# spartan6-0.net
KiCad netlist of a schematic drawn in Altium Designer
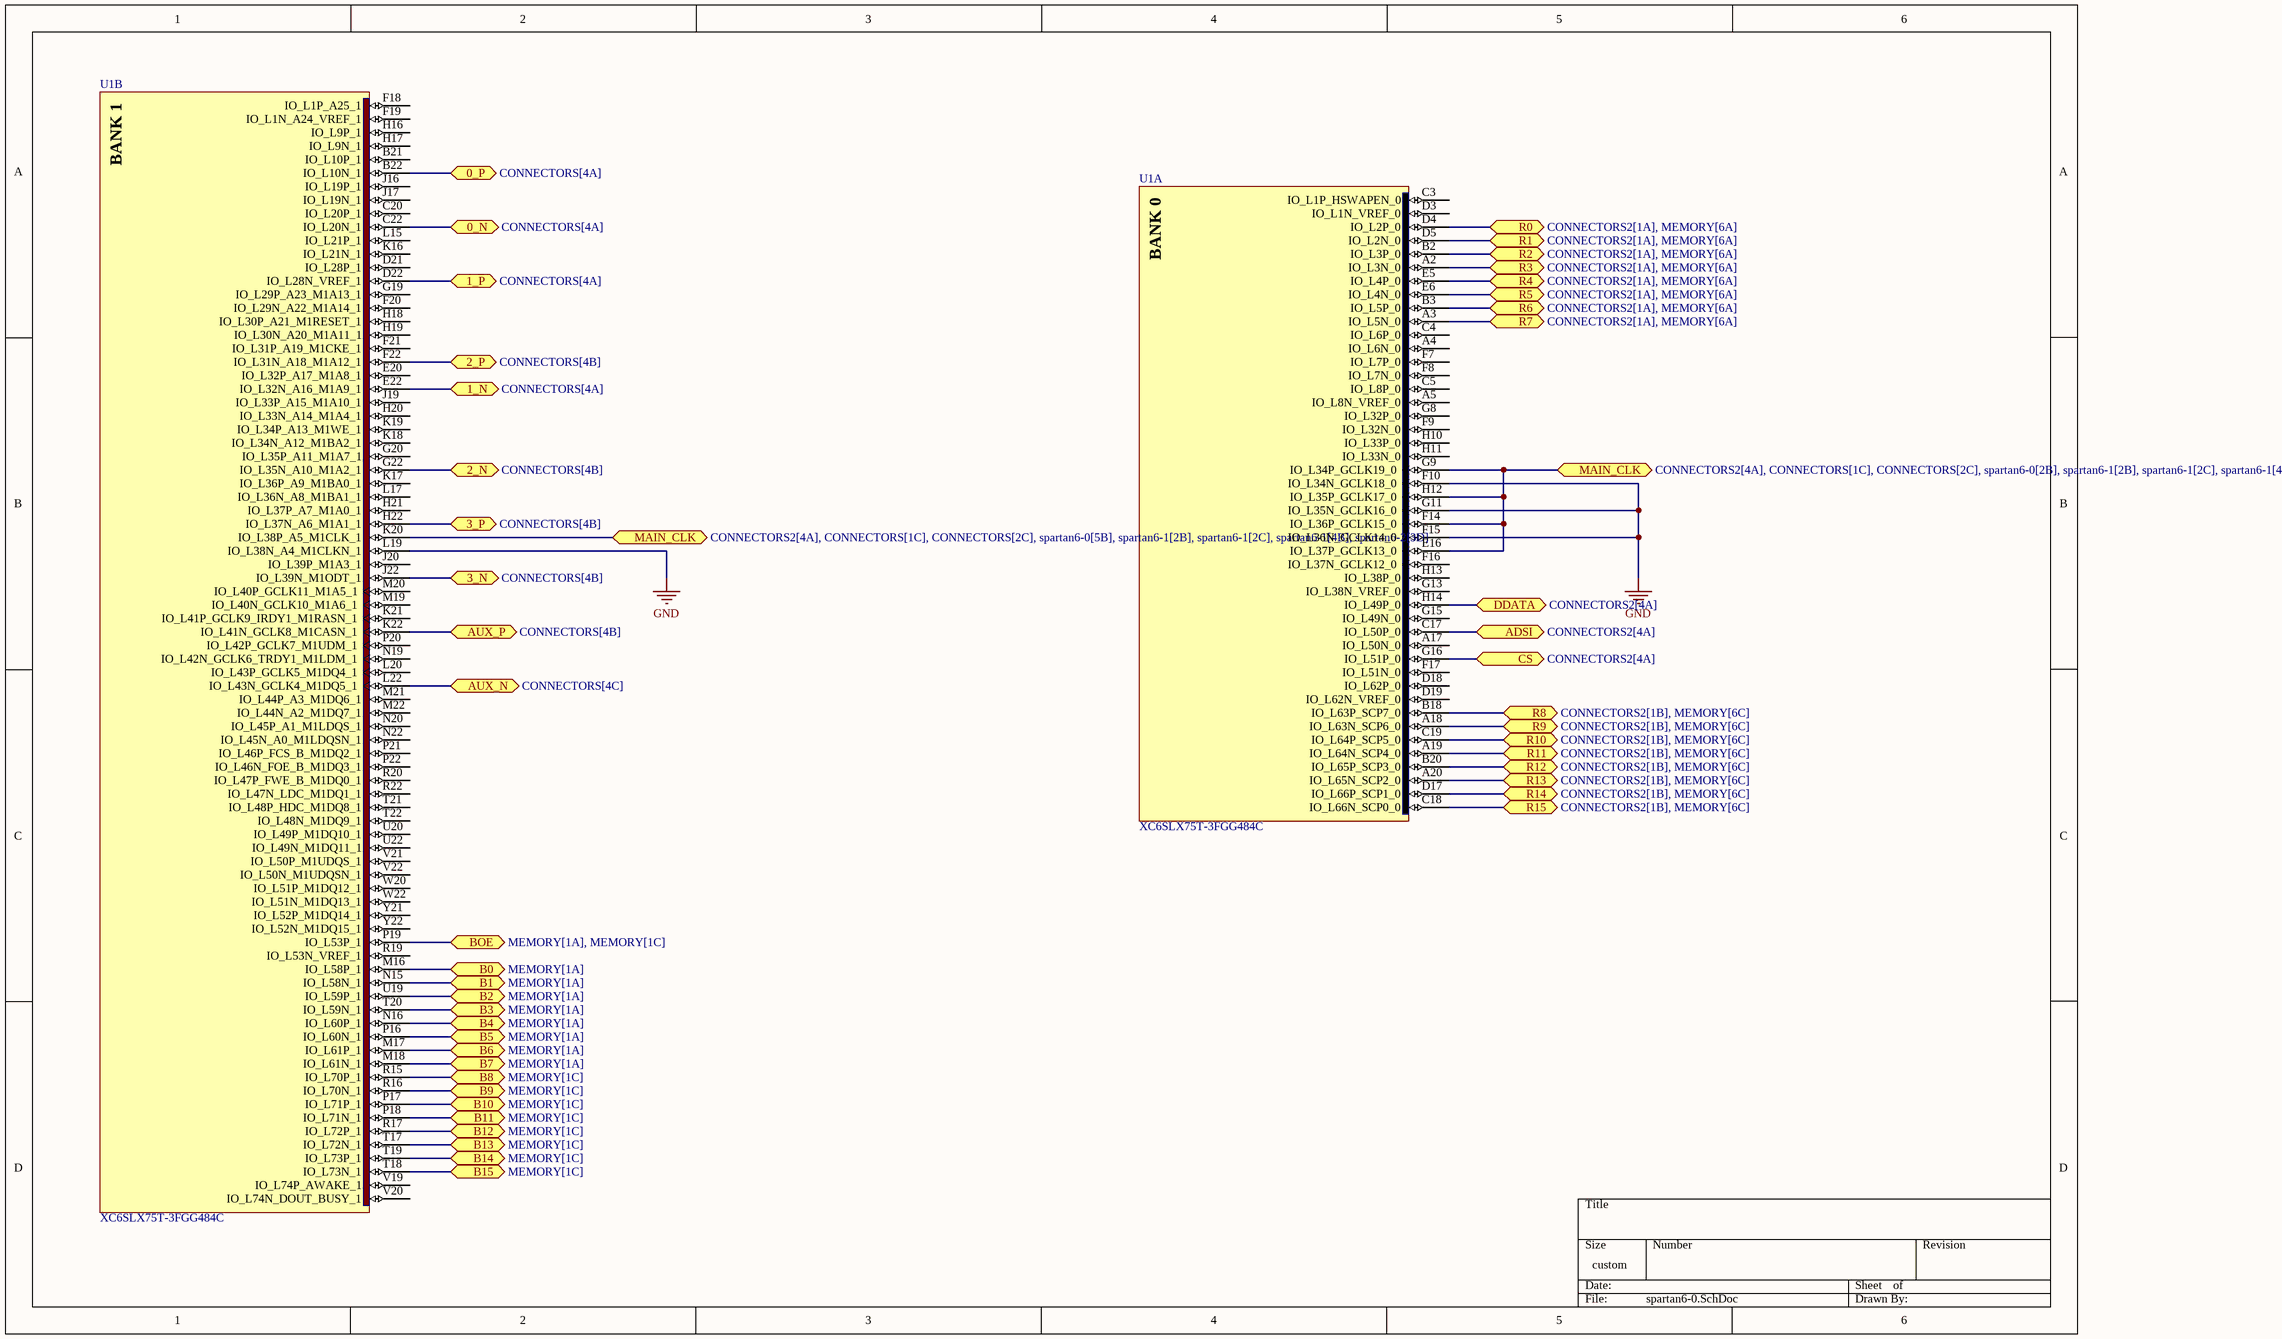
[diagram p0: spartan6-0.SchDoc]

(export (version "E")
  (design (tool "Eeschema 10.0.6"))
  (components
    (comp (ref "U1")
      (value "XC6SLX75T-3FGG484C")
      (footprint "FGG484")
      (libsource (lib "Altium Content Vault") (part "FPGA-XSP6-XC6SLX75T-GA484"))
    )
  )
  (nets
    (net (code "1") (name "/0_N") (class "Default")
      (node (ref "U1") (pin "C22") (pinfunction "IO_L20N_1_C22") (pintype "bidirectional"))
    )
    (net (code "2") (name "/0_P") (class "Default")
      (node (ref "U1") (pin "B22") (pinfunction "IO_L10N_1_B22") (pintype "bidirectional"))
    )
    (net (code "3") (name "/1_N") (class "Default")
      (node (ref "U1") (pin "E22") (pinfunction "IO_L32N_A16_M1A9_1_E22") (pintype "bidirectional"))
    )
    (net (code "4") (name "/1_P") (class "Default")
      (node (ref "U1") (pin "D22") (pinfunction "IO_L28N_VREF_1_D22") (pintype "bidirectional"))
    )
    (net (code "5") (name "/2_N") (class "Default")
      (node (ref "U1") (pin "G22") (pinfunction "IO_L35N_A10_M1A2_1_G22") (pintype "bidirectional"))
    )
    (net (code "6") (name "/2_P") (class "Default")
      (node (ref "U1") (pin "F22") (pinfunction "IO_L31N_A18_M1A12_1_F22") (pintype "bidirectional"))
    )
    (net (code "7") (name "/3_N") (class "Default")
      (node (ref "U1") (pin "J22") (pinfunction "IO_L39N_M1ODT_1_J22") (pintype "bidirectional"))
    )
    (net (code "8") (name "/3_P") (class "Default")
      (node (ref "U1") (pin "H22") (pinfunction "IO_L37N_A6_M1A1_1_H22") (pintype "bidirectional"))
    )
    (net (code "9") (name "/ADSI") (class "Default")
      (node (ref "U1") (pin "C17") (pinfunction "IO_L50P_0_C17") (pintype "bidirectional"))
    )
    (net (code "10") (name "/AUX_N") (class "Default")
      (node (ref "U1") (pin "L22") (pinfunction "IO_L43N_GCLK4_M1DQ5_1_L22") (pintype "bidirectional"))
    )
    (net (code "11") (name "/AUX_P") (class "Default")
      (node (ref "U1") (pin "K22") (pinfunction "IO_L41N_GCLK8_M1CASN_1_K22") (pintype "bidirectional"))
    )
    (net (code "12") (name "/B0") (class "Default")
      (node (ref "U1") (pin "M16") (pinfunction "IO_L58P_1_M16") (pintype "bidirectional"))
    )
    (net (code "13") (name "/B1") (class "Default")
      (node (ref "U1") (pin "N15") (pinfunction "IO_L58N_1_N15") (pintype "bidirectional"))
    )
    (net (code "14") (name "/B2") (class "Default")
      (node (ref "U1") (pin "U19") (pinfunction "IO_L59P_1_U19") (pintype "bidirectional"))
    )
    (net (code "15") (name "/B3") (class "Default")
      (node (ref "U1") (pin "T20") (pinfunction "IO_L59N_1_T20") (pintype "bidirectional"))
    )
    (net (code "16") (name "/B4") (class "Default")
      (node (ref "U1") (pin "N16") (pinfunction "IO_L60P_1_N16") (pintype "bidirectional"))
    )
    (net (code "17") (name "/B5") (class "Default")
      (node (ref "U1") (pin "P16") (pinfunction "IO_L60N_1_P16") (pintype "bidirectional"))
    )
    (net (code "18") (name "/B6") (class "Default")
      (node (ref "U1") (pin "M17") (pinfunction "IO_L61P_1_M17") (pintype "bidirectional"))
    )
    (net (code "19") (name "/B7") (class "Default")
      (node (ref "U1") (pin "M18") (pinfunction "IO_L61N_1_M18") (pintype "bidirectional"))
    )
    (net (code "20") (name "/B8") (class "Default")
      (node (ref "U1") (pin "R15") (pinfunction "IO_L70P_1_R15") (pintype "bidirectional"))
    )
    (net (code "21") (name "/B9") (class "Default")
      (node (ref "U1") (pin "R16") (pinfunction "IO_L70N_1_R16") (pintype "bidirectional"))
    )
    (net (code "22") (name "/B10") (class "Default")
      (node (ref "U1") (pin "P17") (pinfunction "IO_L71P_1_P17") (pintype "bidirectional"))
    )
    (net (code "23") (name "/B11") (class "Default")
      (node (ref "U1") (pin "P18") (pinfunction "IO_L71N_1_P18") (pintype "bidirectional"))
    )
    (net (code "24") (name "/B12") (class "Default")
      (node (ref "U1") (pin "R17") (pinfunction "IO_L72P_1_R17") (pintype "bidirectional"))
    )
    (net (code "25") (name "/B13") (class "Default")
      (node (ref "U1") (pin "T17") (pinfunction "IO_L72N_1_T17") (pintype "bidirectional"))
    )
    (net (code "26") (name "/B14") (class "Default")
      (node (ref "U1") (pin "T19") (pinfunction "IO_L73P_1_T19") (pintype "bidirectional"))
    )
    (net (code "27") (name "/B15") (class "Default")
      (node (ref "U1") (pin "T18") (pinfunction "IO_L73N_1_T18") (pintype "bidirectional"))
    )
    (net (code "28") (name "/BOE") (class "Default")
      (node (ref "U1") (pin "P19") (pinfunction "IO_L53P_1_P19") (pintype "bidirectional"))
    )
    (net (code "29") (name "/CS") (class "Default")
      (node (ref "U1") (pin "G16") (pinfunction "IO_L51P_0_G16") (pintype "bidirectional"))
    )
    (net (code "30") (name "/DDATA") (class "Default")
      (node (ref "U1") (pin "H14") (pinfunction "IO_L49P_0_H14") (pintype "bidirectional"))
    )
    (net (code "31") (name "/MAIN_CLK") (class "Default")
      (node (ref "U1") (pin "E16") (pinfunction "IO_L37P_GCLK13_0_E16") (pintype "bidirectional"))
      (node (ref "U1") (pin "F14") (pinfunction "IO_L36P_GCLK15_0_F14") (pintype "bidirectional"))
      (node (ref "U1") (pin "G9") (pinfunction "IO_L34P_GCLK19_0_G9") (pintype "bidirectional"))
      (node (ref "U1") (pin "H12") (pinfunction "IO_L35P_GCLK17_0_H12") (pintype "bidirectional"))
      (node (ref "U1") (pin "K20") (pinfunction "IO_L38P_A5_M1CLK_1_K20") (pintype "bidirectional"))
    )
    (net (code "32") (name "/R0") (class "Default")
      (node (ref "U1") (pin "D4") (pinfunction "IO_L2P_0_D4") (pintype "bidirectional"))
    )
    (net (code "33") (name "/R1") (class "Default")
      (node (ref "U1") (pin "D5") (pinfunction "IO_L2N_0_D5") (pintype "bidirectional"))
    )
    (net (code "34") (name "/R2") (class "Default")
      (node (ref "U1") (pin "B2") (pinfunction "IO_L3P_0_B2") (pintype "bidirectional"))
    )
    (net (code "35") (name "/R3") (class "Default")
      (node (ref "U1") (pin "A2") (pinfunction "IO_L3N_0_A2") (pintype "bidirectional"))
    )
    (net (code "36") (name "/R4") (class "Default")
      (node (ref "U1") (pin "E5") (pinfunction "IO_L4P_0_E5") (pintype "bidirectional"))
    )
    (net (code "37") (name "/R5") (class "Default")
      (node (ref "U1") (pin "E6") (pinfunction "IO_L4N_0_E6") (pintype "bidirectional"))
    )
    (net (code "38") (name "/R6") (class "Default")
      (node (ref "U1") (pin "B3") (pinfunction "IO_L5P_0_B3") (pintype "bidirectional"))
    )
    (net (code "39") (name "/R7") (class "Default")
      (node (ref "U1") (pin "A3") (pinfunction "IO_L5N_0_A3") (pintype "bidirectional"))
    )
    (net (code "40") (name "/R8") (class "Default")
      (node (ref "U1") (pin "B18") (pinfunction "IO_L63P_SCP7_0_B18") (pintype "bidirectional"))
    )
    (net (code "41") (name "/R9") (class "Default")
      (node (ref "U1") (pin "A18") (pinfunction "IO_L63N_SCP6_0_A18") (pintype "bidirectional"))
    )
    (net (code "42") (name "/R10") (class "Default")
      (node (ref "U1") (pin "C19") (pinfunction "IO_L64P_SCP5_0_C19") (pintype "bidirectional"))
    )
    (net (code "43") (name "/R11") (class "Default")
      (node (ref "U1") (pin "A19") (pinfunction "IO_L64N_SCP4_0_A19") (pintype "bidirectional"))
    )
    (net (code "44") (name "/R12") (class "Default")
      (node (ref "U1") (pin "B20") (pinfunction "IO_L65P_SCP3_0_B20") (pintype "bidirectional"))
    )
    (net (code "45") (name "/R13") (class "Default")
      (node (ref "U1") (pin "A20") (pinfunction "IO_L65N_SCP2_0_A20") (pintype "bidirectional"))
    )
    (net (code "46") (name "/R14") (class "Default")
      (node (ref "U1") (pin "D17") (pinfunction "IO_L66P_SCP1_0_D17") (pintype "bidirectional"))
    )
    (net (code "47") (name "/R15") (class "Default")
      (node (ref "U1") (pin "C18") (pinfunction "IO_L66N_SCP0_0_C18") (pintype "bidirectional"))
    )
    (net (code "48") (name "GND") (class "Default")
      (node (ref "U1") (pin "F10") (pinfunction "IO_L34N_GCLK18_0_F10") (pintype "bidirectional"))
      (node (ref "U1") (pin "F15") (pinfunction "IO_L36N_GCLK14_0_F15") (pintype "bidirectional"))
      (node (ref "U1") (pin "G11") (pinfunction "IO_L35N_GCLK16_0_G11") (pintype "bidirectional"))
      (node (ref "U1") (pin "L19") (pinfunction "IO_L38N_A4_M1CLKN_1_L19") (pintype "bidirectional"))
    )
    (net (code "49") (name "unconnected-(U1A-IO_L1N_VREF_0-PadD3)") (class "Default")
      (node (ref "U1") (pin "D3") (pinfunction "IO_L1N_VREF_0_D3") (pintype "bidirectional"))
    )
    (net (code "50") (name "unconnected-(U1A-IO_L1P_HSWAPEN_0-PadC3)") (class "Default")
      (node (ref "U1") (pin "C3") (pinfunction "IO_L1P_HSWAPEN_0_C3") (pintype "bidirectional"))
    )
    (net (code "51") (name "unconnected-(U1A-IO_L6N_0-PadA4)") (class "Default")
      (node (ref "U1") (pin "A4") (pinfunction "IO_L6N_0_A4") (pintype "bidirectional"))
    )
    (net (code "52") (name "unconnected-(U1A-IO_L6P_0-PadC4)") (class "Default")
      (node (ref "U1") (pin "C4") (pinfunction "IO_L6P_0_C4") (pintype "bidirectional"))
    )
    (net (code "53") (name "unconnected-(U1A-IO_L7N_0-PadF8)") (class "Default")
      (node (ref "U1") (pin "F8") (pinfunction "IO_L7N_0_F8") (pintype "bidirectional"))
    )
    (net (code "54") (name "unconnected-(U1A-IO_L7P_0-PadF7)") (class "Default")
      (node (ref "U1") (pin "F7") (pinfunction "IO_L7P_0_F7") (pintype "bidirectional"))
    )
    (net (code "55") (name "unconnected-(U1A-IO_L8N_VREF_0-PadA5)") (class "Default")
      (node (ref "U1") (pin "A5") (pinfunction "IO_L8N_VREF_0_A5") (pintype "bidirectional"))
    )
    (net (code "56") (name "unconnected-(U1A-IO_L8P_0-PadC5)") (class "Default")
      (node (ref "U1") (pin "C5") (pinfunction "IO_L8P_0_C5") (pintype "bidirectional"))
    )
    (net (code "57") (name "unconnected-(U1A-IO_L32N_0-PadF9)") (class "Default")
      (node (ref "U1") (pin "F9") (pinfunction "IO_L32N_0_F9") (pintype "bidirectional"))
    )
    (net (code "58") (name "unconnected-(U1A-IO_L32P_0-PadG8)") (class "Default")
      (node (ref "U1") (pin "G8") (pinfunction "IO_L32P_0_G8") (pintype "bidirectional"))
    )
    (net (code "59") (name "unconnected-(U1A-IO_L33N_0-PadH11)") (class "Default")
      (node (ref "U1") (pin "H11") (pinfunction "IO_L33N_0_H11") (pintype "bidirectional"))
    )
    (net (code "60") (name "unconnected-(U1A-IO_L33P_0-PadH10)") (class "Default")
      (node (ref "U1") (pin "H10") (pinfunction "IO_L33P_0_H10") (pintype "bidirectional"))
    )
    (net (code "61") (name "unconnected-(U1A-IO_L37N_GCLK12_0-PadF16)") (class "Default")
      (node (ref "U1") (pin "F16") (pinfunction "IO_L37N_GCLK12_0_F16") (pintype "bidirectional"))
    )
    (net (code "62") (name "unconnected-(U1A-IO_L38N_VREF_0-PadG13)") (class "Default")
      (node (ref "U1") (pin "G13") (pinfunction "IO_L38N_VREF_0_G13") (pintype "bidirectional"))
    )
    (net (code "63") (name "unconnected-(U1A-IO_L38P_0-PadH13)") (class "Default")
      (node (ref "U1") (pin "H13") (pinfunction "IO_L38P_0_H13") (pintype "bidirectional"))
    )
    (net (code "64") (name "unconnected-(U1A-IO_L49N_0-PadG15)") (class "Default")
      (node (ref "U1") (pin "G15") (pinfunction "IO_L49N_0_G15") (pintype "bidirectional"))
    )
    (net (code "65") (name "unconnected-(U1A-IO_L50N_0-PadA17)") (class "Default")
      (node (ref "U1") (pin "A17") (pinfunction "IO_L50N_0_A17") (pintype "bidirectional"))
    )
    (net (code "66") (name "unconnected-(U1A-IO_L51N_0-PadF17)") (class "Default")
      (node (ref "U1") (pin "F17") (pinfunction "IO_L51N_0_F17") (pintype "bidirectional"))
    )
    (net (code "67") (name "unconnected-(U1A-IO_L62N_VREF_0-PadD19)") (class "Default")
      (node (ref "U1") (pin "D19") (pinfunction "IO_L62N_VREF_0_D19") (pintype "bidirectional"))
    )
    (net (code "68") (name "unconnected-(U1A-IO_L62P_0-PadD18)") (class "Default")
      (node (ref "U1") (pin "D18") (pinfunction "IO_L62P_0_D18") (pintype "bidirectional"))
    )
    (net (code "69") (name "unconnected-(U1B-IO_L1N_A24_VREF_1-PadF19)") (class "Default")
      (node (ref "U1") (pin "F19") (pinfunction "IO_L1N_A24_VREF_1_F19") (pintype "bidirectional"))
    )
    (net (code "70") (name "unconnected-(U1B-IO_L1P_A25_1-PadF18)") (class "Default")
      (node (ref "U1") (pin "F18") (pinfunction "IO_L1P_A25_1_F18") (pintype "bidirectional"))
    )
    (net (code "71") (name "unconnected-(U1B-IO_L9N_1-PadH17)") (class "Default")
      (node (ref "U1") (pin "H17") (pinfunction "IO_L9N_1_H17") (pintype "bidirectional"))
    )
    (net (code "72") (name "unconnected-(U1B-IO_L9P_1-PadH16)") (class "Default")
      (node (ref "U1") (pin "H16") (pinfunction "IO_L9P_1_H16") (pintype "bidirectional"))
    )
    (net (code "73") (name "unconnected-(U1B-IO_L10P_1-PadB21)") (class "Default")
      (node (ref "U1") (pin "B21") (pinfunction "IO_L10P_1_B21") (pintype "bidirectional"))
    )
    (net (code "74") (name "unconnected-(U1B-IO_L19N_1-PadJ17)") (class "Default")
      (node (ref "U1") (pin "J17") (pinfunction "IO_L19N_1_J17") (pintype "bidirectional"))
    )
    (net (code "75") (name "unconnected-(U1B-IO_L19P_1-PadJ16)") (class "Default")
      (node (ref "U1") (pin "J16") (pinfunction "IO_L19P_1_J16") (pintype "bidirectional"))
    )
    (net (code "76") (name "unconnected-(U1B-IO_L20P_1-PadC20)") (class "Default")
      (node (ref "U1") (pin "C20") (pinfunction "IO_L20P_1_C20") (pintype "bidirectional"))
    )
    (net (code "77") (name "unconnected-(U1B-IO_L21N_1-PadK16)") (class "Default")
      (node (ref "U1") (pin "K16") (pinfunction "IO_L21N_1_K16") (pintype "bidirectional"))
    )
    (net (code "78") (name "unconnected-(U1B-IO_L21P_1-PadL15)") (class "Default")
      (node (ref "U1") (pin "L15") (pinfunction "IO_L21P_1_L15") (pintype "bidirectional"))
    )
    (net (code "79") (name "unconnected-(U1B-IO_L28P_1-PadD21)") (class "Default")
      (node (ref "U1") (pin "D21") (pinfunction "IO_L28P_1_D21") (pintype "bidirectional"))
    )
    (net (code "80") (name "unconnected-(U1B-IO_L29N_A22_M1A14_1-PadF20)") (class "Default")
      (node (ref "U1") (pin "F20") (pinfunction "IO_L29N_A22_M1A14_1_F20") (pintype "bidirectional"))
    )
    (net (code "81") (name "unconnected-(U1B-IO_L29P_A23_M1A13_1-PadG19)") (class "Default")
      (node (ref "U1") (pin "G19") (pinfunction "IO_L29P_A23_M1A13_1_G19") (pintype "bidirectional"))
    )
    (net (code "82") (name "unconnected-(U1B-IO_L30N_A20_M1A11_1-PadH19)") (class "Default")
      (node (ref "U1") (pin "H19") (pinfunction "IO_L30N_A20_M1A11_1_H19") (pintype "bidirectional"))
    )
    (net (code "83") (name "unconnected-(U1B-IO_L30P_A21_M1RESET_1-PadH18)") (class "Default")
      (node (ref "U1") (pin "H18") (pinfunction "IO_L30P_A21_M1RESET_1_H18") (pintype "bidirectional"))
    )
    (net (code "84") (name "unconnected-(U1B-IO_L31P_A19_M1CKE_1-PadF21)") (class "Default")
      (node (ref "U1") (pin "F21") (pinfunction "IO_L31P_A19_M1CKE_1_F21") (pintype "bidirectional"))
    )
    (net (code "85") (name "unconnected-(U1B-IO_L32P_A17_M1A8_1-PadE20)") (class "Default")
      (node (ref "U1") (pin "E20") (pinfunction "IO_L32P_A17_M1A8_1_E20") (pintype "bidirectional"))
    )
    (net (code "86") (name "unconnected-(U1B-IO_L33N_A14_M1A4_1-PadH20)") (class "Default")
      (node (ref "U1") (pin "H20") (pinfunction "IO_L33N_A14_M1A4_1_H20") (pintype "bidirectional"))
    )
    (net (code "87") (name "unconnected-(U1B-IO_L33P_A15_M1A10_1-PadJ19)") (class "Default")
      (node (ref "U1") (pin "J19") (pinfunction "IO_L33P_A15_M1A10_1_J19") (pintype "bidirectional"))
    )
    (net (code "88") (name "unconnected-(U1B-IO_L34N_A12_M1BA2_1-PadK18)") (class "Default")
      (node (ref "U1") (pin "K18") (pinfunction "IO_L34N_A12_M1BA2_1_K18") (pintype "bidirectional"))
    )
    (net (code "89") (name "unconnected-(U1B-IO_L34P_A13_M1WE_1-PadK19)") (class "Default")
      (node (ref "U1") (pin "K19") (pinfunction "IO_L34P_A13_M1WE_1_K19") (pintype "bidirectional"))
    )
    (net (code "90") (name "unconnected-(U1B-IO_L35P_A11_M1A7_1-PadG20)") (class "Default")
      (node (ref "U1") (pin "G20") (pinfunction "IO_L35P_A11_M1A7_1_G20") (pintype "bidirectional"))
    )
    (net (code "91") (name "unconnected-(U1B-IO_L36N_A8_M1BA1_1-PadL17)") (class "Default")
      (node (ref "U1") (pin "L17") (pinfunction "IO_L36N_A8_M1BA1_1_L17") (pintype "bidirectional"))
    )
    (net (code "92") (name "unconnected-(U1B-IO_L36P_A9_M1BA0_1-PadK17)") (class "Default")
      (node (ref "U1") (pin "K17") (pinfunction "IO_L36P_A9_M1BA0_1_K17") (pintype "bidirectional"))
    )
    (net (code "93") (name "unconnected-(U1B-IO_L37P_A7_M1A0_1-PadH21)") (class "Default")
      (node (ref "U1") (pin "H21") (pinfunction "IO_L37P_A7_M1A0_1_H21") (pintype "bidirectional"))
    )
    (net (code "94") (name "unconnected-(U1B-IO_L39P_M1A3_1-PadJ20)") (class "Default")
      (node (ref "U1") (pin "J20") (pinfunction "IO_L39P_M1A3_1_J20") (pintype "bidirectional"))
    )
    (net (code "95") (name "unconnected-(U1B-IO_L40N_GCLK10_M1A6_1-PadM19)") (class "Default")
      (node (ref "U1") (pin "M19") (pinfunction "IO_L40N_GCLK10_M1A6_1_M19") (pintype "bidirectional"))
    )
    (net (code "96") (name "unconnected-(U1B-IO_L40P_GCLK11_M1A5_1-PadM20)") (class "Default")
      (node (ref "U1") (pin "M20") (pinfunction "IO_L40P_GCLK11_M1A5_1_M20") (pintype "bidirectional"))
    )
    (net (code "97") (name "unconnected-(U1B-IO_L41P_GCLK9_IRDY1_M1RASN_1-PadK21)") (class "Default")
      (node (ref "U1") (pin "K21") (pinfunction "IO_L41P_GCLK9_IRDY1_M1RASN_1_K21") (pintype "bidirectional"))
    )
    (net (code "98") (name "unconnected-(U1B-IO_L42N_GCLK6_TRDY1_M1LDM_1-PadN19)") (class "Default")
      (node (ref "U1") (pin "N19") (pinfunction "IO_L42N_GCLK6_TRDY1_M1LDM_1_N19") (pintype "bidirectional"))
    )
    (net (code "99") (name "unconnected-(U1B-IO_L42P_GCLK7_M1UDM_1-PadP20)") (class "Default")
      (node (ref "U1") (pin "P20") (pinfunction "IO_L42P_GCLK7_M1UDM_1_P20") (pintype "bidirectional"))
    )
    (net (code "100") (name "unconnected-(U1B-IO_L43P_GCLK5_M1DQ4_1-PadL20)") (class "Default")
      (node (ref "U1") (pin "L20") (pinfunction "IO_L43P_GCLK5_M1DQ4_1_L20") (pintype "bidirectional"))
    )
    (net (code "101") (name "unconnected-(U1B-IO_L44N_A2_M1DQ7_1-PadM22)") (class "Default")
      (node (ref "U1") (pin "M22") (pinfunction "IO_L44N_A2_M1DQ7_1_M22") (pintype "bidirectional"))
    )
    (net (code "102") (name "unconnected-(U1B-IO_L44P_A3_M1DQ6_1-PadM21)") (class "Default")
      (node (ref "U1") (pin "M21") (pinfunction "IO_L44P_A3_M1DQ6_1_M21") (pintype "bidirectional"))
    )
    (net (code "103") (name "unconnected-(U1B-IO_L45N_A0_M1LDQSN_1-PadN22)") (class "Default")
      (node (ref "U1") (pin "N22") (pinfunction "IO_L45N_A0_M1LDQSN_1_N22") (pintype "bidirectional"))
    )
    (net (code "104") (name "unconnected-(U1B-IO_L45P_A1_M1LDQS_1-PadN20)") (class "Default")
      (node (ref "U1") (pin "N20") (pinfunction "IO_L45P_A1_M1LDQS_1_N20") (pintype "bidirectional"))
    )
    (net (code "105") (name "unconnected-(U1B-IO_L46N_FOE_B_M1DQ3_1-PadP22)") (class "Default")
      (node (ref "U1") (pin "P22") (pinfunction "IO_L46N_FOE_B_M1DQ3_1_P22") (pintype "bidirectional"))
    )
    (net (code "106") (name "unconnected-(U1B-IO_L46P_FCS_B_M1DQ2_1-PadP21)") (class "Default")
      (node (ref "U1") (pin "P21") (pinfunction "IO_L46P_FCS_B_M1DQ2_1_P21") (pintype "bidirectional"))
    )
    (net (code "107") (name "unconnected-(U1B-IO_L47N_LDC_M1DQ1_1-PadR22)") (class "Default")
      (node (ref "U1") (pin "R22") (pinfunction "IO_L47N_LDC_M1DQ1_1_R22") (pintype "bidirectional"))
    )
    (net (code "108") (name "unconnected-(U1B-IO_L47P_FWE_B_M1DQ0_1-PadR20)") (class "Default")
      (node (ref "U1") (pin "R20") (pinfunction "IO_L47P_FWE_B_M1DQ0_1_R20") (pintype "bidirectional"))
    )
    (net (code "109") (name "unconnected-(U1B-IO_L48N_M1DQ9_1-PadT22)") (class "Default")
      (node (ref "U1") (pin "T22") (pinfunction "IO_L48N_M1DQ9_1_T22") (pintype "bidirectional"))
    )
    (net (code "110") (name "unconnected-(U1B-IO_L48P_HDC_M1DQ8_1-PadT21)") (class "Default")
      (node (ref "U1") (pin "T21") (pinfunction "IO_L48P_HDC_M1DQ8_1_T21") (pintype "bidirectional"))
    )
    (net (code "111") (name "unconnected-(U1B-IO_L49N_M1DQ11_1-PadU22)") (class "Default")
      (node (ref "U1") (pin "U22") (pinfunction "IO_L49N_M1DQ11_1_U22") (pintype "bidirectional"))
    )
    (net (code "112") (name "unconnected-(U1B-IO_L49P_M1DQ10_1-PadU20)") (class "Default")
      (node (ref "U1") (pin "U20") (pinfunction "IO_L49P_M1DQ10_1_U20") (pintype "bidirectional"))
    )
    (net (code "113") (name "unconnected-(U1B-IO_L50N_M1UDQSN_1-PadV22)") (class "Default")
      (node (ref "U1") (pin "V22") (pinfunction "IO_L50N_M1UDQSN_1_V22") (pintype "bidirectional"))
    )
    (net (code "114") (name "unconnected-(U1B-IO_L50P_M1UDQS_1-PadV21)") (class "Default")
      (node (ref "U1") (pin "V21") (pinfunction "IO_L50P_M1UDQS_1_V21") (pintype "bidirectional"))
    )
    (net (code "115") (name "unconnected-(U1B-IO_L51N_M1DQ13_1-PadW22)") (class "Default")
      (node (ref "U1") (pin "W22") (pinfunction "IO_L51N_M1DQ13_1_W22") (pintype "bidirectional"))
    )
    (net (code "116") (name "unconnected-(U1B-IO_L51P_M1DQ12_1-PadW20)") (class "Default")
      (node (ref "U1") (pin "W20") (pinfunction "IO_L51P_M1DQ12_1_W20") (pintype "bidirectional"))
    )
    (net (code "117") (name "unconnected-(U1B-IO_L52N_M1DQ15_1-PadY22)") (class "Default")
      (node (ref "U1") (pin "Y22") (pinfunction "IO_L52N_M1DQ15_1_Y22") (pintype "bidirectional"))
    )
    (net (code "118") (name "unconnected-(U1B-IO_L52P_M1DQ14_1-PadY21)") (class "Default")
      (node (ref "U1") (pin "Y21") (pinfunction "IO_L52P_M1DQ14_1_Y21") (pintype "bidirectional"))
    )
    (net (code "119") (name "unconnected-(U1B-IO_L53N_VREF_1-PadR19)") (class "Default")
      (node (ref "U1") (pin "R19") (pinfunction "IO_L53N_VREF_1_R19") (pintype "bidirectional"))
    )
    (net (code "120") (name "unconnected-(U1B-IO_L74N_DOUT_BUSY_1-PadV20)") (class "Default")
      (node (ref "U1") (pin "V20") (pinfunction "IO_L74N_DOUT_BUSY_1_V20") (pintype "bidirectional"))
    )
    (net (code "121") (name "unconnected-(U1B-IO_L74P_AWAKE_1-PadV19)") (class "Default")
      (node (ref "U1") (pin "V19") (pinfunction "IO_L74P_AWAKE_1_V19") (pintype "bidirectional"))
    )
  )
)
